# tweeq-BATT_SR621.net
KiCad netlist of a schematic drawn in EAGLE
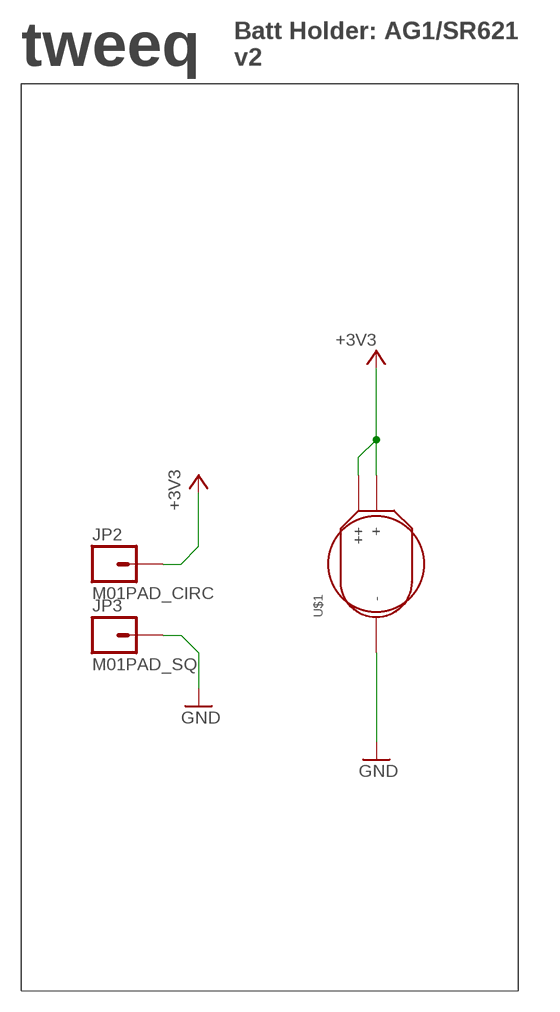
[diagram p0: schematic, sheet 1]

(export (version "E")
  (design (tool "Eeschema 10.0.6"))
  (components
    (comp (ref "JP2")
      (value "M01PAD_CIRC")
      (footprint "eagle-import:1X01_PAD_CIRC")
      (libsource (lib "eagle-import") (part "M01PAD_CIRC"))
    )
    (comp (ref "JP3")
      (value "M01PAD_SQ")
      (footprint "eagle-import:1X01_PAD_SQ")
      (libsource (lib "eagle-import") (part "M01PAD_SQ"))
    )
    (comp (ref "U$1")
      (value "BATT_COMMON/AG1")
      (footprint "eagle-import:BATT_AG1_TH")
      (libsource (lib "eagle-import") (part "BATT_COMMON/AG1"))
    )
  )
  (nets
    (net (code "1") (name "+3V3") (class "Default")
      (node (ref "JP2") (pin "1") (pinfunction "1_1") (pintype "passive"))
      (node (ref "U$1") (pin "+1") (pinfunction "+_+1") (pintype "bidirectional"))
      (node (ref "U$1") (pin "+2") (pinfunction "++_+2") (pintype "bidirectional"))
    )
    (net (code "2") (name "GND") (class "Default")
      (node (ref "JP3") (pin "1") (pinfunction "1_1") (pintype "passive"))
      (node (ref "U$1") (pin "-") (pinfunction "-_-") (pintype "bidirectional"))
    )
  )
)
